# Other.net
KiCad netlist of a schematic drawn in Altium Designer
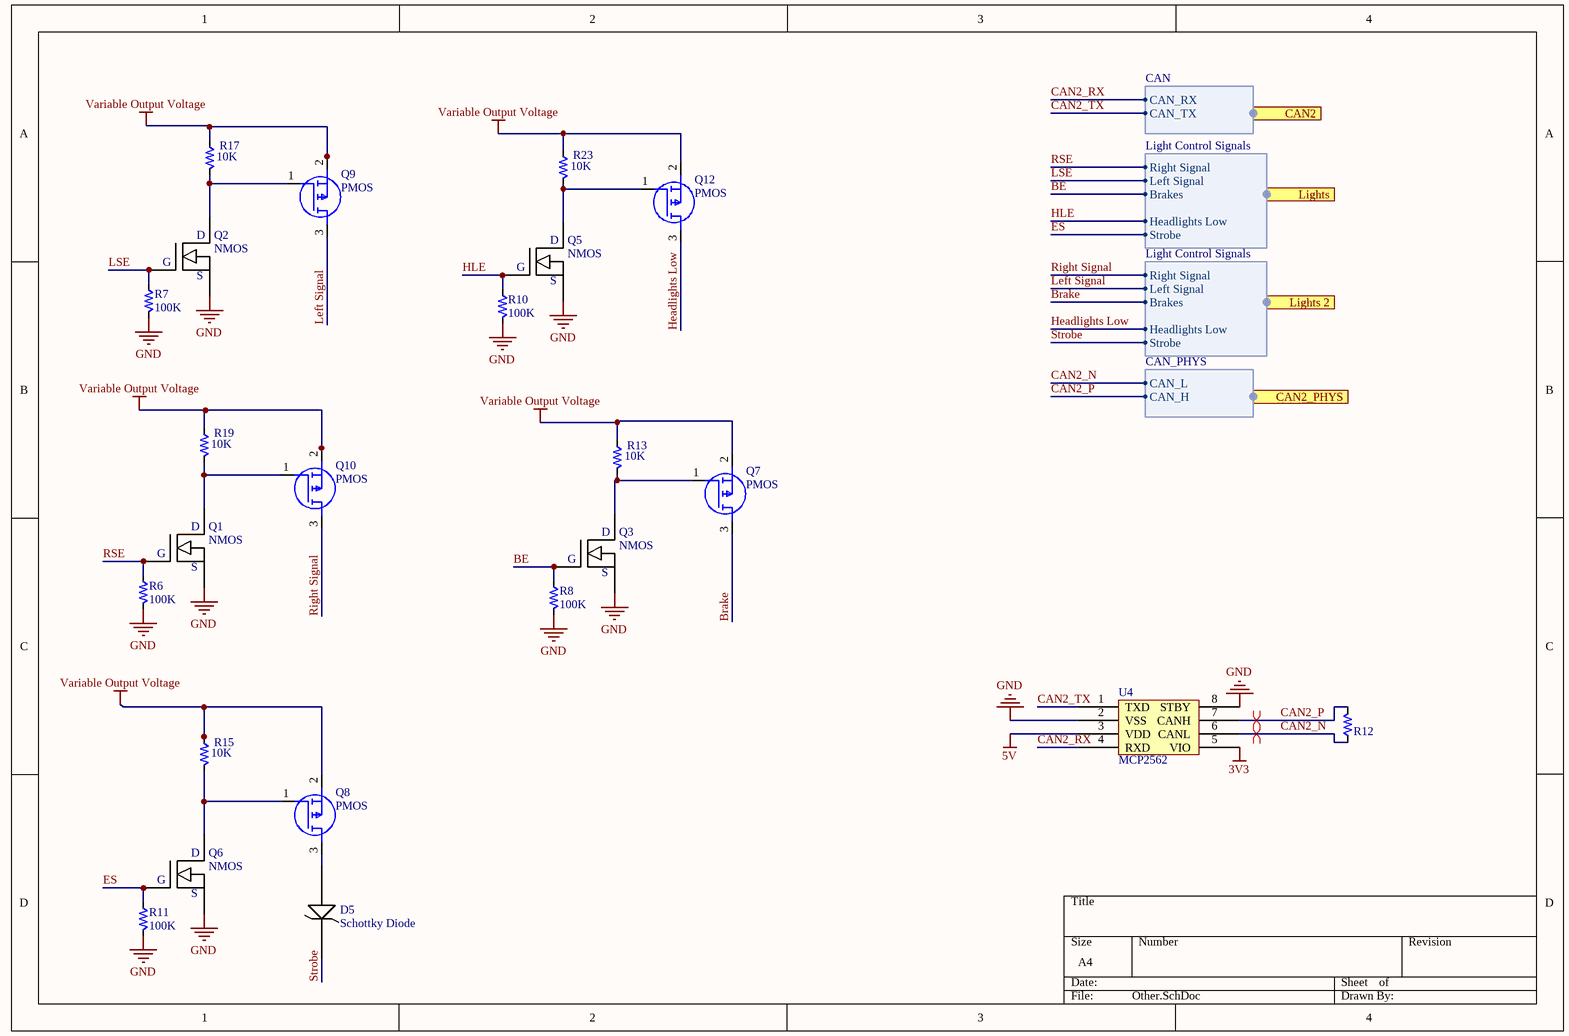
[diagram p0: Other.SchDoc]

(export (version "E")
  (design (tool "Eeschema 10.0.6"))
  (components
    (comp (ref "D5")
      (value "Schottky Diode")
      (footprint "ON Semi Schottky Diode - MBRM110LT1G")
      (libsource (lib "Zener Diode") (part "ON Semi Schottky Diode - MBRM110LT1G"))
    )
    (comp (ref "Q1")
      (value "NMOS")
      (footprint "NMOS - SSM3K333R - SOTFL95P180X88-3M")
      (libsource (lib "NMOS - SSM3K333R - SOTFL95P180X88-3M") (part "NMOS - SSM3K333R"))
    )
    (comp (ref "Q2")
      (value "NMOS")
      (footprint "NMOS - SSM3K333R - SOTFL95P180X88-3M")
      (libsource (lib "NMOS - SSM3K333R - SOTFL95P180X88-3M") (part "NMOS - SSM3K333R"))
    )
    (comp (ref "Q3")
      (value "NMOS")
      (footprint "NMOS - SSM3K333R - SOTFL95P180X88-3M")
      (libsource (lib "NMOS - SSM3K333R - SOTFL95P180X88-3M") (part "NMOS - SSM3K333R"))
    )
    (comp (ref "Q5")
      (value "NMOS")
      (footprint "NMOS - SSM3K333R - SOTFL95P180X88-3M")
      (libsource (lib "NMOS - SSM3K333R - SOTFL95P180X88-3M") (part "NMOS - SSM3K333R"))
    )
    (comp (ref "Q6")
      (value "NMOS")
      (footprint "NMOS - SSM3K333R - SOTFL95P180X88-3M")
      (libsource (lib "NMOS - SSM3K333R - SOTFL95P180X88-3M") (part "NMOS - SSM3K333R"))
    )
    (comp (ref "Q7")
      (value "PMOS")
      (footprint "Toshiba PMOS - SOT23-F:NMOS - SSM3K333R - SOTFL95P180X88-3M")
      (description "MOSFET (P-Channel)")
      (fields
        (field (name "MANUFACTURER_PART_NUMBER") "SSM3J334R,LF(T")
        (field (name "RS PART NUMBER") "1445260P")
      )
      (libsource (lib "Toshiba PMOS - SOT23-F") (part "SSM3J334R,LF(T"))
    )
    (comp (ref "Q8")
      (value "PMOS")
      (footprint "Toshiba PMOS - SOT23-F:NMOS - SSM3K333R - SOTFL95P180X88-3M")
      (description "MOSFET (P-Channel)")
      (fields
        (field (name "MANUFACTURER_PART_NUMBER") "SSM3J334R,LF(T")
        (field (name "RS PART NUMBER") "1445260P")
      )
      (libsource (lib "Toshiba PMOS - SOT23-F") (part "SSM3J334R,LF(T"))
    )
    (comp (ref "Q9")
      (value "PMOS")
      (footprint "Toshiba PMOS - SOT23-F:NMOS - SSM3K333R - SOTFL95P180X88-3M")
      (description "MOSFET (P-Channel)")
      (fields
        (field (name "MANUFACTURER_PART_NUMBER") "SSM3J334R,LF(T")
        (field (name "RS PART NUMBER") "1445260P")
      )
      (libsource (lib "Toshiba PMOS - SOT23-F") (part "SSM3J334R,LF(T"))
    )
    (comp (ref "Q10")
      (value "PMOS")
      (footprint "Toshiba PMOS - SOT23-F:NMOS - SSM3K333R - SOTFL95P180X88-3M")
      (description "MOSFET (P-Channel)")
      (fields
        (field (name "MANUFACTURER_PART_NUMBER") "SSM3J334R,LF(T")
        (field (name "RS PART NUMBER") "1445260P")
      )
      (libsource (lib "Toshiba PMOS - SOT23-F") (part "SSM3J334R,LF(T"))
    )
    (comp (ref "Q12")
      (value "PMOS")
      (footprint "Toshiba PMOS - SOT23-F:NMOS - SSM3K333R - SOTFL95P180X88-3M")
      (description "MOSFET (P-Channel)")
      (fields
        (field (name "MANUFACTURER_PART_NUMBER") "SSM3J334R,LF(T")
        (field (name "RS PART NUMBER") "1445260P")
      )
      (libsource (lib "Toshiba PMOS - SOT23-F") (part "SSM3J334R,LF(T"))
    )
    (comp (ref "R6")
      (value "SCH_GENERIC_RESISTOR_0603")
      (footprint "Generic 0603 Resistor:PCB_GENERIC_SMD_0603")
      (description "Generic SMD resistor 0603")
      (fields (field (name "RESISTANCE") "100K"))
      (libsource (lib "SCH_GENERIC_RESISTOR_0603") (part "SCH_GENERIC_RESISTOR_0603"))
    )
    (comp (ref "R7")
      (value "SCH_GENERIC_RESISTOR_0603")
      (footprint "Generic 0603 Resistor:PCB_GENERIC_SMD_0603")
      (description "Generic SMD resistor 0603")
      (fields (field (name "RESISTANCE") "100K"))
      (libsource (lib "SCH_GENERIC_RESISTOR_0603") (part "SCH_GENERIC_RESISTOR_0603"))
    )
    (comp (ref "R8")
      (value "SCH_GENERIC_RESISTOR_0603")
      (footprint "Generic 0603 Resistor:PCB_GENERIC_SMD_0603")
      (description "Generic SMD resistor 0603")
      (fields (field (name "RESISTANCE") "100K"))
      (libsource (lib "SCH_GENERIC_RESISTOR_0603") (part "SCH_GENERIC_RESISTOR_0603"))
    )
    (comp (ref "R10")
      (value "SCH_GENERIC_RESISTOR_0603")
      (footprint "Generic 0603 Resistor:PCB_GENERIC_SMD_0603")
      (description "Generic SMD resistor 0603")
      (fields (field (name "RESISTANCE") "100K"))
      (libsource (lib "SCH_GENERIC_RESISTOR_0603") (part "SCH_GENERIC_RESISTOR_0603"))
    )
    (comp (ref "R11")
      (value "SCH_GENERIC_RESISTOR_0603")
      (footprint "Generic 0603 Resistor:PCB_GENERIC_SMD_0603")
      (description "Generic SMD resistor 0603")
      (fields (field (name "RESISTANCE") "100K"))
      (libsource (lib "SCH_GENERIC_RESISTOR_0603") (part "SCH_GENERIC_RESISTOR_0603"))
    )
    (comp (ref "R12")
      (value "SCH_GENERIC_RESISTOR_0603")
      (footprint "Generic 0603 Resistor:PCB_GENERIC_SMD_0603")
      (description "Generic SMD resistor 0603")
      (libsource (lib "Generic 0603 Resistor") (part "SCH_GENERIC_RESISTOR_0603"))
    )
    (comp (ref "R13")
      (value "SCH_GENERIC_RESISTOR_0603")
      (footprint "Generic 0603 Resistor:PCB_GENERIC_SMD_0603")
      (description "Generic SMD resistor 0603")
      (fields (field (name "RESISTANCE") "10K"))
      (libsource (lib "SCH_GENERIC_RESISTOR_0603") (part "SCH_GENERIC_RESISTOR_0603"))
    )
    (comp (ref "R15")
      (value "SCH_GENERIC_RESISTOR_0603")
      (footprint "Generic 0603 Resistor:PCB_GENERIC_SMD_0603")
      (description "Generic SMD resistor 0603")
      (fields (field (name "RESISTANCE") "10K"))
      (libsource (lib "SCH_GENERIC_RESISTOR_0603") (part "SCH_GENERIC_RESISTOR_0603"))
    )
    (comp (ref "R17")
      (value "SCH_GENERIC_RESISTOR_0603")
      (footprint "Generic 0603 Resistor:PCB_GENERIC_SMD_0603")
      (description "Generic SMD resistor 0603")
      (fields (field (name "RESISTANCE") "10K"))
      (libsource (lib "SCH_GENERIC_RESISTOR_0603") (part "SCH_GENERIC_RESISTOR_0603"))
    )
    (comp (ref "R19")
      (value "SCH_GENERIC_RESISTOR_0603")
      (footprint "Generic 0603 Resistor:PCB_GENERIC_SMD_0603")
      (description "Generic SMD resistor 0603")
      (fields (field (name "RESISTANCE") "10K"))
      (libsource (lib "SCH_GENERIC_RESISTOR_0603") (part "SCH_GENERIC_RESISTOR_0603"))
    )
    (comp (ref "R23")
      (value "SCH_GENERIC_RESISTOR_0603")
      (footprint "Generic 0603 Resistor:PCB_GENERIC_SMD_0603")
      (description "Generic SMD resistor 0603")
      (fields (field (name "RESISTANCE") "10K"))
      (libsource (lib "SCH_GENERIC_RESISTOR_0603") (part "SCH_GENERIC_RESISTOR_0603"))
    )
    (comp (ref "U4") (value "MCP2562") (footprint "MCP2562") (libsource (lib "MCP2562_SCH") (part "MCP2562")))
  )
  (nets
    (net (code "6") (name "/BE") (class "Default")
      (node (ref "Q3") (pin "1") (pinfunction "G_1") (pintype "passive"))
      (node (ref "R8") (pin "1") (pinfunction "1_1") (pintype "passive"))
    )
    (net (code "7") (name "/Brake") (class "Default")
      (node (ref "Q7") (pin "3") (pinfunction "3_3") (pintype "passive"))
    )
    (net (code "8") (name "/CAN2_N") (class "Default")
      (node (ref "R12") (pin "1") (pinfunction "1_1") (pintype "passive"))
      (node (ref "U4") (pin "6") (pinfunction "CANL_6") (pintype "passive"))
    )
    (net (code "9") (name "/CAN2_P") (class "Default")
      (node (ref "R12") (pin "2") (pinfunction "2_2") (pintype "passive"))
      (node (ref "U4") (pin "7") (pinfunction "CANH_7") (pintype "passive"))
    )
    (net (code "10") (name "/CAN2_RX") (class "Default")
      (node (ref "U4") (pin "4") (pinfunction "RXD_4") (pintype "passive"))
    )
    (net (code "11") (name "/CAN2_TX") (class "Default")
      (node (ref "U4") (pin "1") (pinfunction "TXD_1") (pintype "passive"))
    )
    (net (code "12") (name "/ES") (class "Default")
      (node (ref "Q6") (pin "1") (pinfunction "G_1") (pintype "passive"))
      (node (ref "R11") (pin "1") (pinfunction "1_1") (pintype "passive"))
    )
    (net (code "13") (name "/HLE") (class "Default")
      (node (ref "Q5") (pin "1") (pinfunction "G_1") (pintype "passive"))
      (node (ref "R10") (pin "1") (pinfunction "1_1") (pintype "passive"))
    )
    (net (code "14") (name "/Headlights Low") (class "Default")
      (node (ref "Q12") (pin "3") (pinfunction "3_3") (pintype "passive"))
    )
    (net (code "15") (name "/LSE") (class "Default")
      (node (ref "Q2") (pin "1") (pinfunction "G_1") (pintype "passive"))
      (node (ref "R7") (pin "1") (pinfunction "1_1") (pintype "passive"))
    )
    (net (code "16") (name "/Left Signal") (class "Default")
      (node (ref "Q9") (pin "3") (pinfunction "3_3") (pintype "passive"))
    )
    (net (code "17") (name "/RSE") (class "Default")
      (node (ref "Q1") (pin "1") (pinfunction "G_1") (pintype "passive"))
      (node (ref "R6") (pin "1") (pinfunction "1_1") (pintype "passive"))
    )
    (net (code "18") (name "/Right Signal") (class "Default")
      (node (ref "Q10") (pin "3") (pinfunction "3_3") (pintype "passive"))
    )
    (net (code "19") (name "/Strobe") (class "Default")
      (node (ref "D5") (pin "1") (pinfunction "1_1") (pintype "passive"))
    )
    (net (code "23") (name "3V3") (class "Default")
      (node (ref "U4") (pin "5") (pinfunction "VIO_5") (pintype "passive"))
    )
    (net (code "24") (name "5V") (class "Default")
      (node (ref "U4") (pin "3") (pinfunction "VDD_3") (pintype "passive"))
    )
    (net (code "25") (name "GND") (class "Default")
      (node (ref "Q1") (pin "2") (pinfunction "S_2") (pintype "passive"))
      (node (ref "Q2") (pin "2") (pinfunction "S_2") (pintype "passive"))
      (node (ref "Q3") (pin "2") (pinfunction "S_2") (pintype "passive"))
      (node (ref "Q5") (pin "2") (pinfunction "S_2") (pintype "passive"))
      (node (ref "Q6") (pin "2") (pinfunction "S_2") (pintype "passive"))
      (node (ref "R10") (pin "2") (pinfunction "2_2") (pintype "passive"))
      (node (ref "R11") (pin "2") (pinfunction "2_2") (pintype "passive"))
      (node (ref "R6") (pin "2") (pinfunction "2_2") (pintype "passive"))
      (node (ref "R7") (pin "2") (pinfunction "2_2") (pintype "passive"))
      (node (ref "R8") (pin "2") (pinfunction "2_2") (pintype "passive"))
      (node (ref "U4") (pin "2") (pinfunction "VSS_2") (pintype "passive"))
      (node (ref "U4") (pin "8") (pinfunction "STBY_8") (pintype "passive"))
    )
    (net (code "26") (name "Net-(D5-Pad2)") (class "Default")
      (node (ref "D5") (pin "2") (pinfunction "2_2") (pintype "passive"))
      (node (ref "Q8") (pin "3") (pinfunction "3_3") (pintype "passive"))
    )
    (net (code "27") (name "Net-(Q1-D)") (class "Default")
      (node (ref "Q1") (pin "3") (pinfunction "D_3") (pintype "passive"))
      (node (ref "Q10") (pin "1") (pinfunction "1_1") (pintype "passive"))
      (node (ref "R19") (pin "2") (pinfunction "2_2") (pintype "passive"))
    )
    (net (code "28") (name "Net-(Q2-D)") (class "Default")
      (node (ref "Q2") (pin "3") (pinfunction "D_3") (pintype "passive"))
      (node (ref "Q9") (pin "1") (pinfunction "1_1") (pintype "passive"))
      (node (ref "R17") (pin "2") (pinfunction "2_2") (pintype "passive"))
    )
    (net (code "29") (name "Net-(Q3-D)") (class "Default")
      (node (ref "Q3") (pin "3") (pinfunction "D_3") (pintype "passive"))
      (node (ref "Q7") (pin "1") (pinfunction "1_1") (pintype "passive"))
      (node (ref "R13") (pin "2") (pinfunction "2_2") (pintype "passive"))
    )
    (net (code "30") (name "Net-(Q5-D)") (class "Default")
      (node (ref "Q12") (pin "1") (pinfunction "1_1") (pintype "passive"))
      (node (ref "Q5") (pin "3") (pinfunction "D_3") (pintype "passive"))
      (node (ref "R23") (pin "2") (pinfunction "2_2") (pintype "passive"))
    )
    (net (code "31") (name "Net-(Q6-D)") (class "Default")
      (node (ref "Q6") (pin "3") (pinfunction "D_3") (pintype "passive"))
      (node (ref "Q8") (pin "1") (pinfunction "1_1") (pintype "passive"))
      (node (ref "R15") (pin "2") (pinfunction "2_2") (pintype "passive"))
    )
    (net (code "32") (name "Variable Output Voltage") (class "Default")
      (node (ref "Q10") (pin "2") (pinfunction "2_2") (pintype "passive"))
      (node (ref "Q12") (pin "2") (pinfunction "2_2") (pintype "passive"))
      (node (ref "Q7") (pin "2") (pinfunction "2_2") (pintype "passive"))
      (node (ref "Q8") (pin "2") (pinfunction "2_2") (pintype "passive"))
      (node (ref "Q9") (pin "2") (pinfunction "2_2") (pintype "passive"))
      (node (ref "R13") (pin "1") (pinfunction "1_1") (pintype "passive"))
      (node (ref "R15") (pin "1") (pinfunction "1_1") (pintype "passive"))
      (node (ref "R17") (pin "1") (pinfunction "1_1") (pintype "passive"))
      (node (ref "R19") (pin "1") (pinfunction "1_1") (pintype "passive"))
      (node (ref "R23") (pin "1") (pinfunction "1_1") (pintype "passive"))
    )
  )
)
